# Power_Supply.net
KiCad netlist of a schematic drawn in Altium Designer
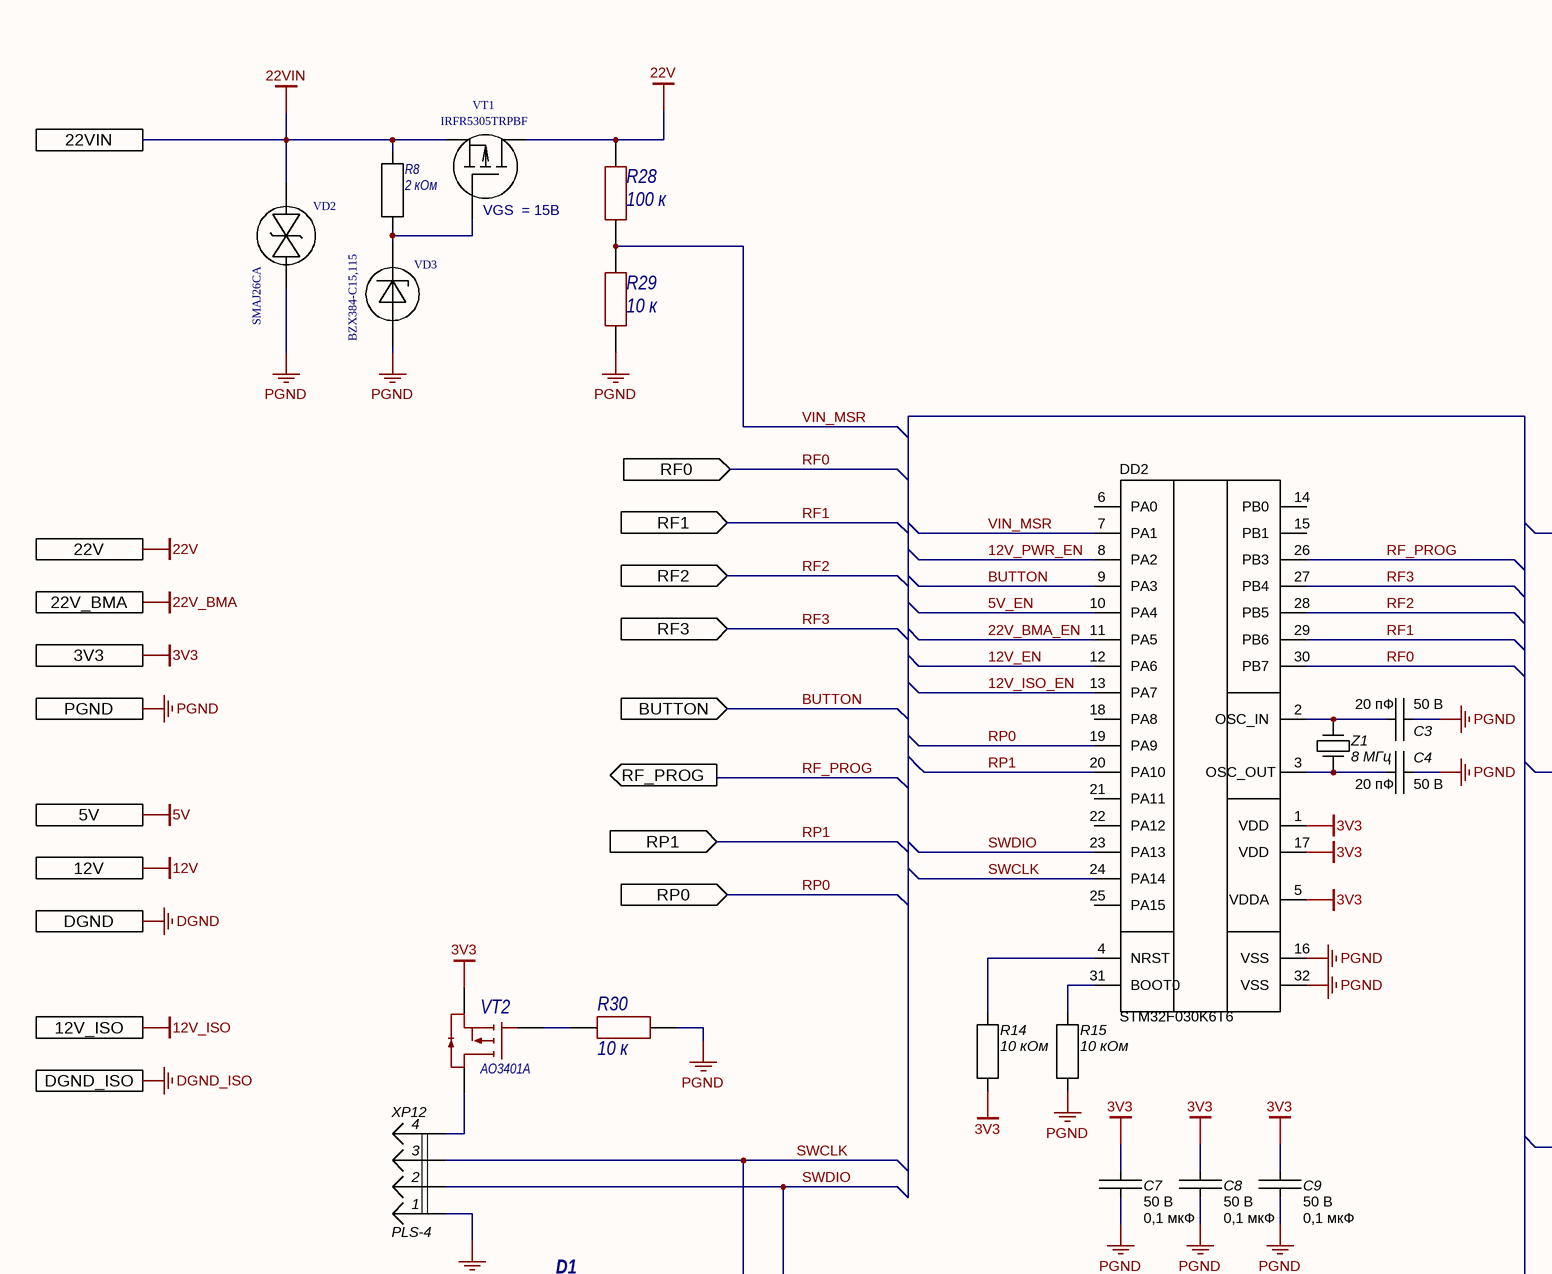
[diagram p0: Power Supply.SchDoc, top left]
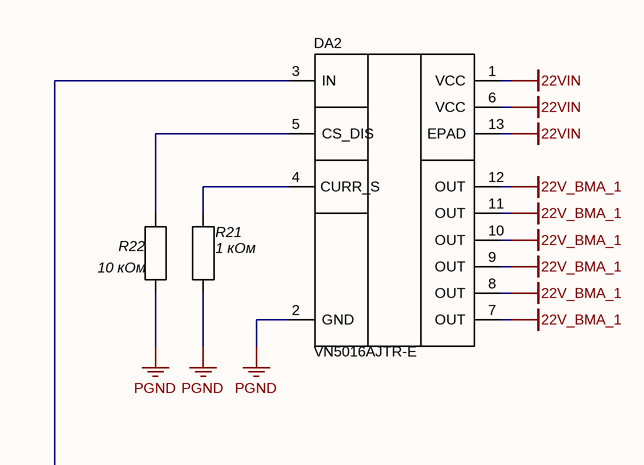
[diagram p1: Power Supply.SchDoc, top right]
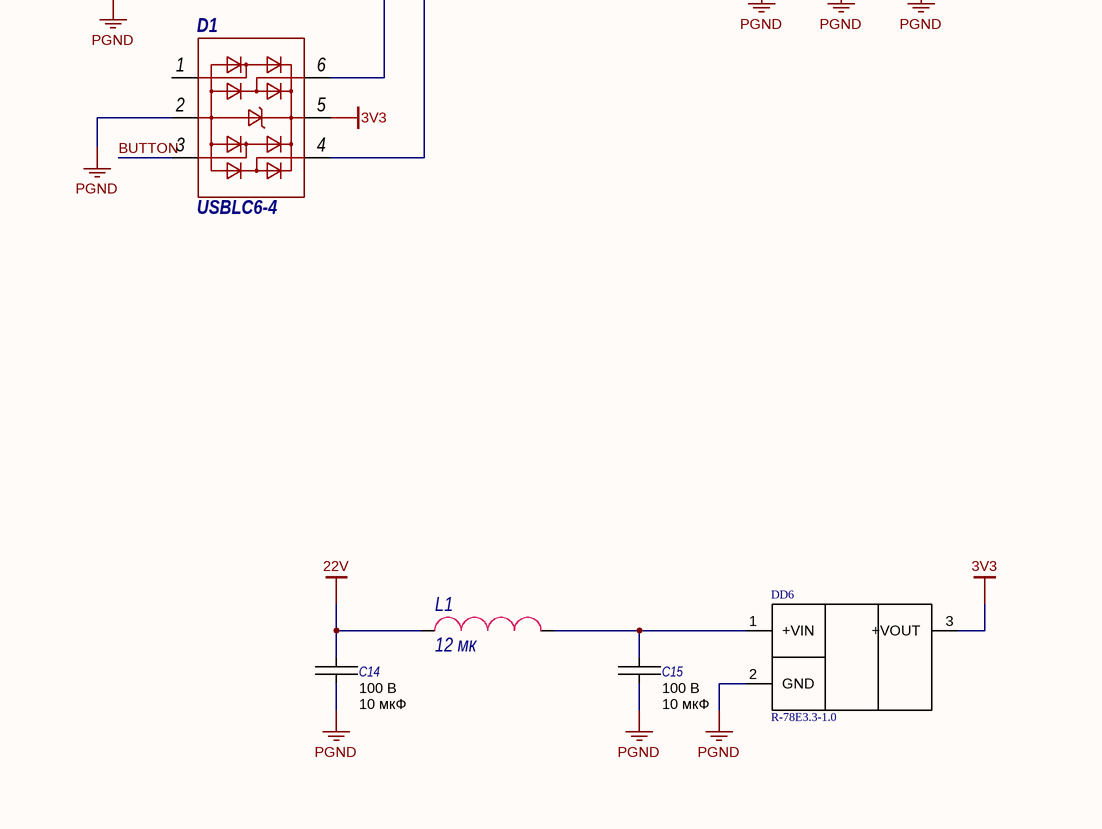
[diagram p2: Power Supply.SchDoc, bottom left]
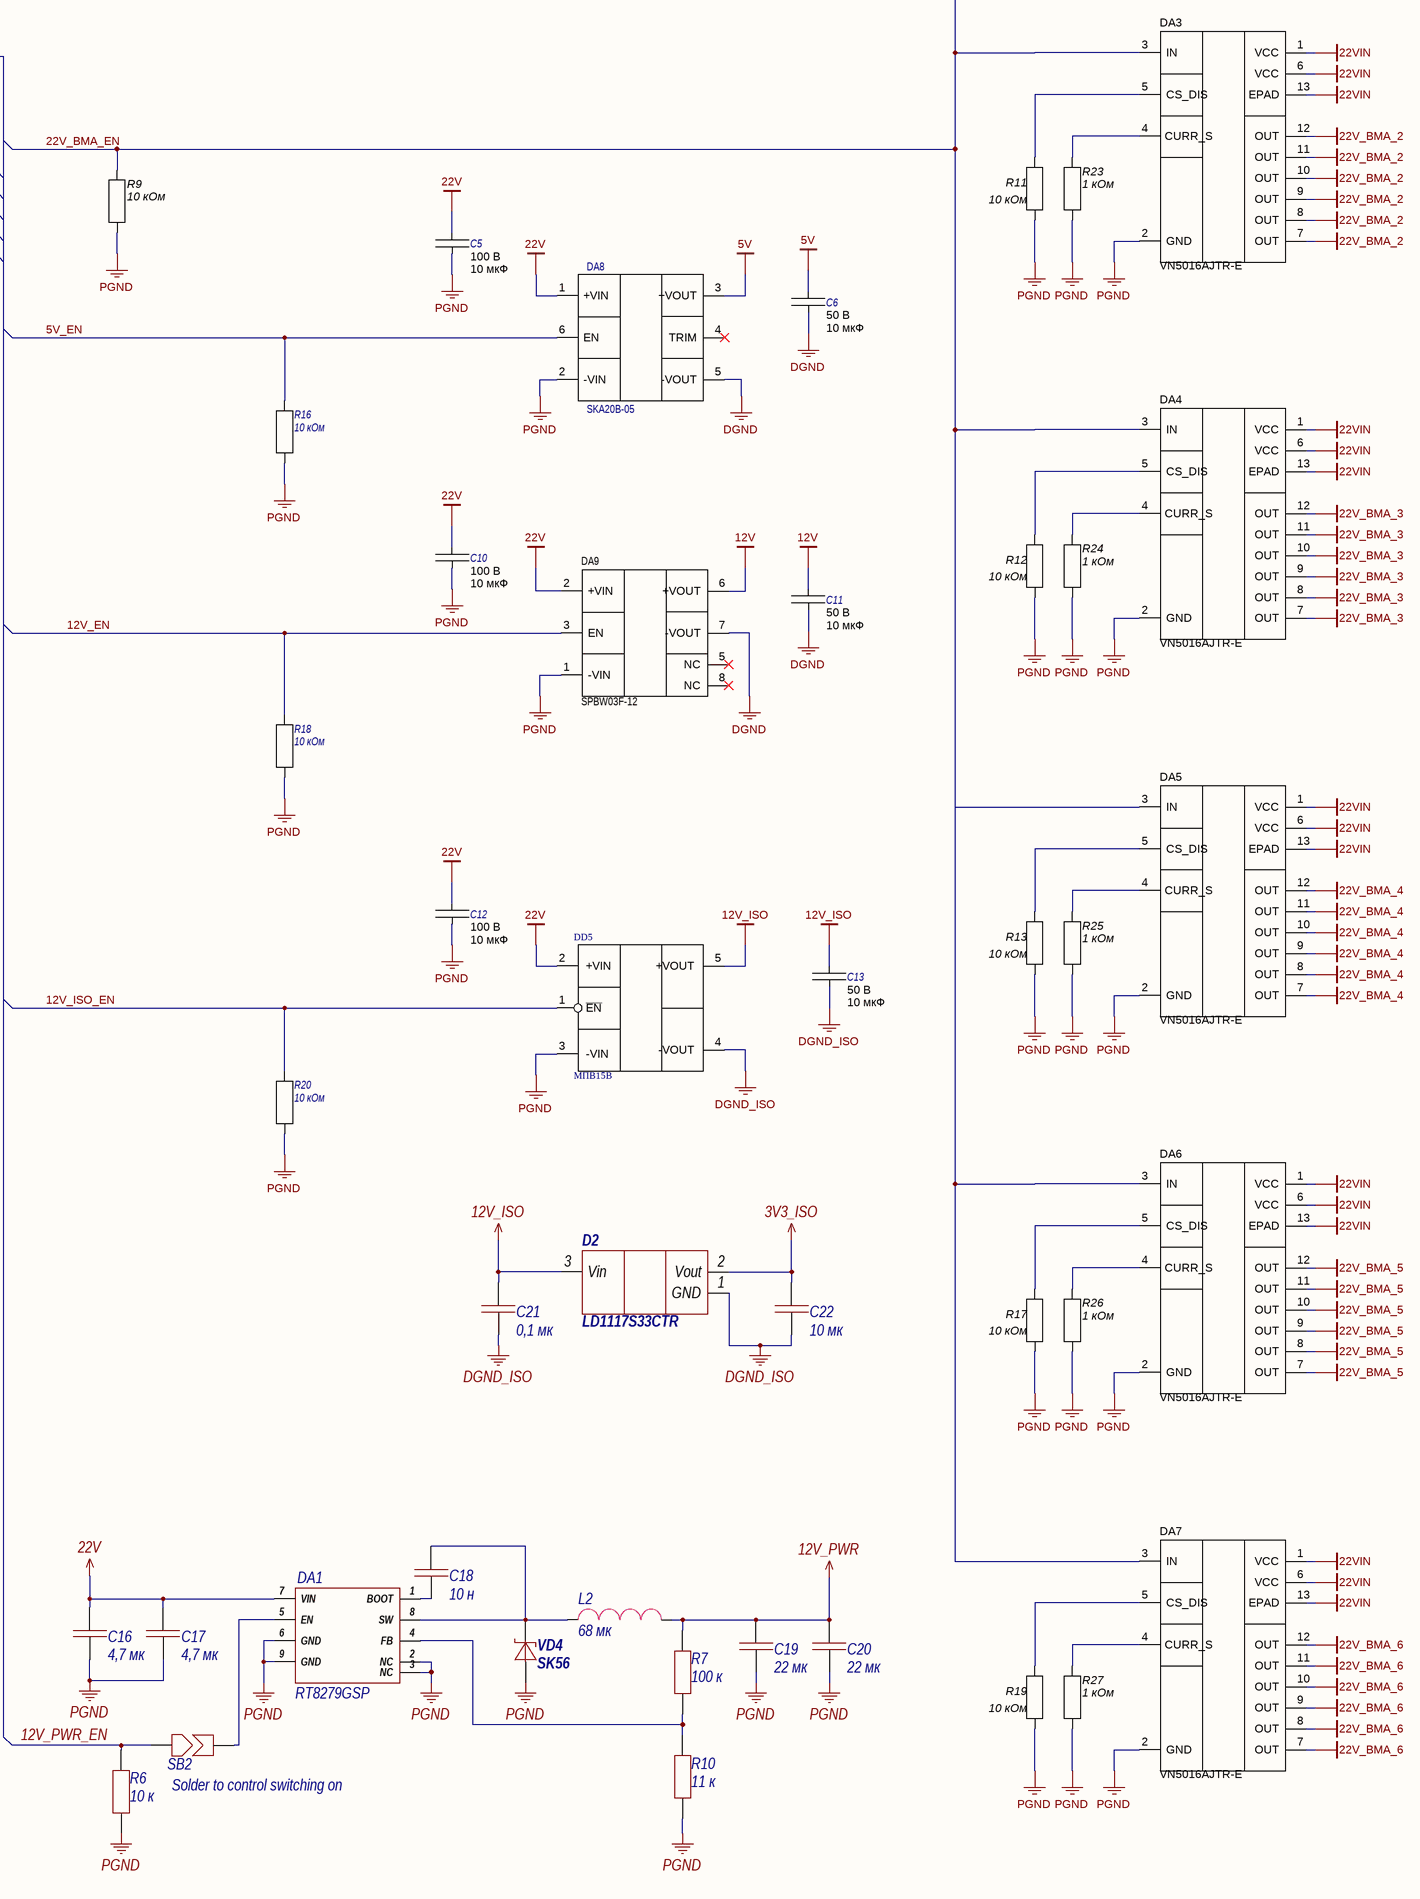
[diagram p3: Power Supply.SchDoc, bottom right]

(export (version "E")
  (design (tool "Eeschema 10.0.6"))
  (components
    (comp (ref "C3")
      (value "20 пФ")
      (footprint "C0603C")
      (description "SMD 0603 ; C0G(NP0); 20 пФ; 50 В")
      (fields
        (field (name "PART NUMBER") "CC0603JRNPO9BN200")
        (field (name "MANUFACTURER") "YAGEO")
        (field (name "VOLTAGE") "50 В")
      )
      (libsource (lib "Capacitors") (part "CC0603JRNPO9BN200"))
    )
    (comp (ref "C4")
      (value "20 пФ")
      (footprint "C0603C")
      (description "SMD 0603 ; C0G(NP0); 20 пФ; 50 В")
      (fields
        (field (name "PART NUMBER") "CC0603JRNPO9BN200")
        (field (name "MANUFACTURER") "YAGEO")
        (field (name "VOLTAGE") "50 В")
      )
      (libsource (lib "Capacitors") (part "CC0603JRNPO9BN200"))
    )
    (comp (ref "C5")
      (value "10 мкФ")
      (footprint "C2220C")
      (description "SMD 2220 ; X7R; 10 мкФ; 100 В")
      (fields
        (field (name "PART NUMBER") "22201C106MAT2A")
        (field (name "MANUFACTURER") "AVX")
        (field (name "VOLTAGE") "100 В")
      )
      (libsource (lib "Capacitors") (part "22201C106MAT2A"))
    )
    (comp (ref "C6")
      (value "10 мкФ")
      (footprint "C1210C")
      (description "SMD 1210; X7R; 10 мкФ; 50 В")
      (fields
        (field (name "PART NUMBER") "12105C106KAT2A")
        (field (name "MANUFACTURER") "AVX")
        (field (name "VOLTAGE") "50 В")
      )
      (libsource (lib "Capacitors") (part "12105C106KAT2A"))
    )
    (comp (ref "C7")
      (value "0,1 мкФ")
      (footprint "C0603C")
      (description "SMD 0603 ; X7R; 0,1 мкФ; 50 В")
      (fields
        (field (name "PART NUMBER") "CC0603KRX7R9BB104")
        (field (name "MANUFACTURER") "YAGEO")
        (field (name "VOLTAGE") "50 В")
      )
      (libsource (lib "Capacitors") (part "CC0603KRX7R9BB104"))
    )
    (comp (ref "C8")
      (value "0,1 мкФ")
      (footprint "C0603C")
      (description "SMD 0603 ; X7R; 0,1 мкФ; 50 В")
      (fields
        (field (name "PART NUMBER") "CC0603KRX7R9BB104")
        (field (name "MANUFACTURER") "YAGEO")
        (field (name "VOLTAGE") "50 В")
      )
      (libsource (lib "Capacitors") (part "CC0603KRX7R9BB104"))
    )
    (comp (ref "C9")
      (value "0,1 мкФ")
      (footprint "C0603C")
      (description "SMD 0603 ; X7R; 0,1 мкФ; 50 В")
      (fields
        (field (name "PART NUMBER") "CC0603KRX7R9BB104")
        (field (name "MANUFACTURER") "YAGEO")
        (field (name "VOLTAGE") "50 В")
      )
      (libsource (lib "Capacitors") (part "CC0603KRX7R9BB104"))
    )
    (comp (ref "C10")
      (value "10 мкФ")
      (footprint "C2220C")
      (description "SMD 2220 ; X7R; 10 мкФ; 100 В")
      (fields
        (field (name "PART NUMBER") "22201C106MAT2A")
        (field (name "MANUFACTURER") "AVX")
        (field (name "VOLTAGE") "100 В")
      )
      (libsource (lib "Capacitors") (part "22201C106MAT2A"))
    )
    (comp (ref "C11")
      (value "10 мкФ")
      (footprint "C1210C")
      (description "SMD 1210; X7R; 10 мкФ; 50 В")
      (fields
        (field (name "PART NUMBER") "12105C106KAT2A")
        (field (name "MANUFACTURER") "AVX")
        (field (name "VOLTAGE") "50 В")
      )
      (libsource (lib "Capacitors") (part "12105C106KAT2A"))
    )
    (comp (ref "C12")
      (value "10 мкФ")
      (footprint "C2220C")
      (description "SMD 2220 ; X7R; 10 мкФ; 100 В")
      (fields
        (field (name "PART NUMBER") "22201C106MAT2A")
        (field (name "MANUFACTURER") "AVX")
        (field (name "VOLTAGE") "100 В")
      )
      (libsource (lib "Capacitors") (part "22201C106MAT2A"))
    )
    (comp (ref "C13")
      (value "10 мкФ")
      (footprint "C1210C")
      (description "SMD 1210; X7R; 10 мкФ; 50 В")
      (fields
        (field (name "PART NUMBER") "12105C106KAT2A")
        (field (name "MANUFACTURER") "AVX")
        (field (name "VOLTAGE") "50 В")
      )
      (libsource (lib "Capacitors") (part "12105C106KAT2A"))
    )
    (comp (ref "C14")
      (value "10 мкФ")
      (footprint "C2220C")
      (description "SMD 2220 ; X7R; 10 мкФ; 100 В")
      (fields
        (field (name "PART NUMBER") "22201C106MAT2A")
        (field (name "MANUFACTURER") "AVX")
        (field (name "VOLTAGE") "100 В")
      )
      (libsource (lib "Capacitors") (part "22201C106MAT2A"))
    )
    (comp (ref "C15")
      (value "10 мкФ")
      (footprint "C2220C")
      (description "SMD 2220 ; X7R; 10 мкФ; 100 В")
      (fields
        (field (name "PART NUMBER") "22201C106MAT2A")
        (field (name "MANUFACTURER") "AVX")
        (field (name "VOLTAGE") "100 В")
      )
      (libsource (lib "Capacitors") (part "22201C106MAT2A"))
    )
    (comp (ref "C16")
      (value "4,7 мк")
      (footprint "1206C")
      (description "Конденсатор")
      (fields (field (name "PART NUMBER") "Capacitor_4,7u_10_50V_X7R_1206C") (field (name "TOLERANCE") "0,1"))
      (libsource (lib "Hydrolib") (part "Capacitor"))
    )
    (comp (ref "C17")
      (value "4,7 мк")
      (footprint "1206C")
      (description "Конденсатор")
      (fields (field (name "PART NUMBER") "Capacitor_4,7u_10_50V_X7R_1206C") (field (name "TOLERANCE") "0,1"))
      (libsource (lib "Hydrolib") (part "Capacitor"))
    )
    (comp (ref "C18")
      (value "10 н")
      (footprint "0603C")
      (description "Конденсатор")
      (fields (field (name "PART NUMBER") "Capacitor_10n_10_50V_X7R_0603C") (field (name "TOLERANCE") "0,1"))
      (libsource (lib "Hydrolib") (part "Capacitor"))
    )
    (comp (ref "C19")
      (value "22 мк")
      (footprint "1210C")
      (description "Конденсатор")
      (fields (field (name "PART NUMBER") "Capacitor_22u_10_25V_X7R_1210C") (field (name "TOLERANCE") "0,1"))
      (libsource (lib "Hydrolib") (part "Capacitor"))
    )
    (comp (ref "C20")
      (value "22 мк")
      (footprint "1210C")
      (description "Конденсатор")
      (fields (field (name "PART NUMBER") "Capacitor_22u_10_25V_X7R_1210C") (field (name "TOLERANCE") "0,1"))
      (libsource (lib "Hydrolib") (part "Capacitor"))
    )
    (comp (ref "C21")
      (value "0,1 мк")
      (footprint "0603C")
      (description "Конденсатор")
      (fields (field (name "PART NUMBER") "Capacitor_0,1u_10_50V_X7R_0603C") (field (name "TOLERANCE") "0,1"))
      (libsource (lib "Hydrolib") (part "Capacitor"))
    )
    (comp (ref "C22")
      (value "10 мк")
      (footprint "1210C")
      (description "Конденсатор")
      (fields (field (name "PART NUMBER") "Capacitor_10u_10_35V_X7R_1210C") (field (name "TOLERANCE") "0,1"))
      (libsource (lib "Hydrolib") (part "Capacitor"))
    )
    (comp (ref "D1")
      (value "USBLC6-4")
      (footprint "SOT23-6")
      (description "Сборка защитных диодов для USB")
      (libsource (lib "Hydrolib") (part "USBLC6-4"))
    )
    (comp (ref "D2")
      (value "LD1117S33CTR")
      (footprint "SOT223")
      (description "Линейный стабилизатор напряжения")
      (libsource (lib "Hydrolib") (part "LD1117S33CTR"))
    )
    (comp (ref "DA1")
      (value "RT8279GSP")
      (footprint "8SOP(Exposed_Pad)")
      (description "Преобразователь постоянного тока понижающий подстраиваемый выход 5А")
      (libsource (lib "Hydrolib") (part "RT8279GSP"))
    )
    (comp (ref "DA2")
      (value "VN5016AJTR-E")
      (footprint "PowerSSO-12")
      (description "High Current Power Switch")
      (fields (field (name "MANUFACTURER") "STMicroelectronics"))
      (libsource (lib "IC") (part "VN5016AJTR-E"))
    )
    (comp (ref "DA3")
      (value "VN5016AJTR-E")
      (footprint "PowerSSO-12")
      (description "High Current Power Switch")
      (fields (field (name "MANUFACTURER") "STMicroelectronics"))
      (libsource (lib "IC") (part "VN5016AJTR-E"))
    )
    (comp (ref "DA4")
      (value "VN5016AJTR-E")
      (footprint "PowerSSO-12")
      (description "High Current Power Switch")
      (fields (field (name "MANUFACTURER") "STMicroelectronics"))
      (libsource (lib "IC") (part "VN5016AJTR-E"))
    )
    (comp (ref "DA5")
      (value "VN5016AJTR-E")
      (footprint "PowerSSO-12")
      (description "High Current Power Switch")
      (fields (field (name "MANUFACTURER") "STMicroelectronics"))
      (libsource (lib "IC") (part "VN5016AJTR-E"))
    )
    (comp (ref "DA6")
      (value "VN5016AJTR-E")
      (footprint "PowerSSO-12")
      (description "High Current Power Switch")
      (fields (field (name "MANUFACTURER") "STMicroelectronics"))
      (libsource (lib "IC") (part "VN5016AJTR-E"))
    )
    (comp (ref "DA7")
      (value "VN5016AJTR-E")
      (footprint "PowerSSO-12")
      (description "High Current Power Switch")
      (fields (field (name "MANUFACTURER") "STMicroelectronics"))
      (libsource (lib "IC") (part "VN5016AJTR-E"))
    )
    (comp (ref "DA8")
      (value "SKA20B-05")
      (footprint "SKA20B05")
      (description "SKA20B-05, DC/DC преобразователь, 20Вт, вход 18-36В,выход 5В/4А")
      (libsource (lib "SKA20B-05") (part "Component_1"))
    )
    (comp (ref "DA9")
      (value "SPBW03F-12")
      (footprint "SIP8")
      (description "SPBW03F-12, DC/DC преобразователь, 3Вт, вход 9-36В,выход 12В/0.25А")
      (libsource (lib "SPBW03F-12") (part "SPBW03F-12"))
    )
    (comp (ref "DD2")
      (value "STM32F030K6T6")
      (footprint "LQFP32")
      (fields (field (name "MANUFACTURER") "STMicroelectronics"))
      (libsource (lib "IC") (part "STM32F030K6T6"))
    )
    (comp (ref "DD5")
      (value "МПВ15В")
      (footprint "МП_15_")
      (description "Switching regulator, Uвх = 27В, Uвых =12V")
      (fields (field (name "MANUFACTURER") "ИРБИС"))
      (libsource (lib "IC") (part "МПВ15В"))
    )
    (comp (ref "DD6")
      (value "R-78E3.3-1.0")
      (footprint "SIP3")
      (description "DC/DC, 24VIN 3V3 OUT")
      (fields (field (name "MANUFACTURER") "Recom"))
      (libsource (lib "IC") (part "R-78E3.3-1.0"))
    )
    (comp (ref "L1")
      (value "12 мк")
      (footprint "4.5x4_wired")
      (description "Индуктивность на 12 мкГн, номинальный ток 1,05 A")
      (fields (field (name "PART NUMBER") "SDR0403-120ML"))
      (libsource (lib "Hydrolib") (part "Inductance"))
    )
    (comp (ref "L2")
      (value "68 мк")
      (footprint "12.5x12.5")
      (description "Индуктивность на 68 мкГн, номинальный ток 2,65 A")
      (fields (field (name "PART NUMBER") "B82477R4683M100"))
      (libsource (lib "Hydrolib") (part "Inductance"))
    )
    (comp (ref "R6")
      (value "10 к")
      (footprint "0603R")
      (description "Резистор номиналом 10 кОм и точностью 1%")
      (fields (field (name "PART NUMBER") "Resistor_10k_1_0603") (field (name "TOLERANCE") "1%"))
      (libsource (lib "Hydrolib") (part "Resistor"))
    )
    (comp (ref "R7")
      (value "100 к")
      (footprint "0603R")
      (description "Резистор номиналом 100 кОм и точностью 1%")
      (fields (field (name "PART NUMBER") "Resistor_100k_1_0603") (field (name "TOLERANCE") "1%"))
      (libsource (lib "Hydrolib") (part "Resistor"))
    )
    (comp (ref "R8")
      (value "2 кОм")
      (footprint "C0603R")
      (description "SMD 0603; 0,1; 1%; 2 кОм")
      (fields (field (name "PART NUMBER") "RC0603FR-072KL") (field (name "POWER") "0,1"))
      (libsource (lib "Resistors") (part "RC0603FR-072KL"))
    )
    (comp (ref "R9")
      (value "10 кОм")
      (footprint "C0603R")
      (description "SMD 0603; 0,1; 1%; 10 кОм")
      (fields (field (name "PART NUMBER") "RC0603FR-0710KL") (field (name "POWER") "0,1"))
      (libsource (lib "Resistors") (part "RC0603FR-0710KL"))
    )
    (comp (ref "R10")
      (value "11 к")
      (footprint "0603R")
      (description "Резистор номиналом 11 кОм и точностью 1%")
      (fields (field (name "PART NUMBER") "Resistor_11k_1_0603") (field (name "TOLERANCE") "1%"))
      (libsource (lib "") (part "Resistor_2"))
    )
    (comp (ref "R11")
      (value "10 кОм")
      (footprint "C0603R")
      (description "SMD 0603; 0,1; 1%; 10 кОм")
      (fields (field (name "PART NUMBER") "RC0603FR-0710KL") (field (name "POWER") "0,1"))
      (libsource (lib "Resistors") (part "RC0603FR-0710KL"))
    )
    (comp (ref "R12")
      (value "10 кОм")
      (footprint "C0603R")
      (description "SMD 0603; 0,1; 1%; 10 кОм")
      (fields (field (name "PART NUMBER") "RC0603FR-0710KL") (field (name "POWER") "0,1"))
      (libsource (lib "Resistors") (part "RC0603FR-0710KL"))
    )
    (comp (ref "R13")
      (value "10 кОм")
      (footprint "C0603R")
      (description "SMD 0603; 0,1; 1%; 10 кОм")
      (fields (field (name "PART NUMBER") "RC0603FR-0710KL") (field (name "POWER") "0,1"))
      (libsource (lib "Resistors") (part "RC0603FR-0710KL"))
    )
    (comp (ref "R14")
      (value "10 кОм")
      (footprint "C0603R")
      (description "SMD 0603; 0,1; 1%; 10 кОм")
      (fields (field (name "PART NUMBER") "RC0603FR-0710KL") (field (name "POWER") "0,1"))
      (libsource (lib "Resistors") (part "RC0603FR-0710KL"))
    )
    (comp (ref "R15")
      (value "10 кОм")
      (footprint "C0603R")
      (description "SMD 0603; 0,1; 1%; 10 кОм")
      (fields (field (name "PART NUMBER") "RC0603FR-0710KL") (field (name "POWER") "0,1"))
      (libsource (lib "Resistors") (part "RC0603FR-0710KL"))
    )
    (comp (ref "R16")
      (value "10 кОм")
      (footprint "C0603R")
      (description "SMD 0603; 0,1; 1%; 10 кОм")
      (fields (field (name "PART NUMBER") "RC0603FR-0710KL") (field (name "POWER") "0,1"))
      (libsource (lib "Resistors") (part "RC0603FR-0710KL"))
    )
    (comp (ref "R17")
      (value "10 кОм")
      (footprint "C0603R")
      (description "SMD 0603; 0,1; 1%; 10 кОм")
      (fields (field (name "PART NUMBER") "RC0603FR-0710KL") (field (name "POWER") "0,1"))
      (libsource (lib "Resistors") (part "RC0603FR-0710KL"))
    )
    (comp (ref "R18")
      (value "10 кОм")
      (footprint "C0603R")
      (description "SMD 0603; 0,1; 1%; 10 кОм")
      (fields (field (name "PART NUMBER") "RC0603FR-0710KL") (field (name "POWER") "0,1"))
      (libsource (lib "Resistors") (part "RC0603FR-0710KL"))
    )
    (comp (ref "R19")
      (value "10 кОм")
      (footprint "C0603R")
      (description "SMD 0603; 0,1; 1%; 10 кОм")
      (fields (field (name "PART NUMBER") "RC0603FR-0710KL") (field (name "POWER") "0,1"))
      (libsource (lib "Resistors") (part "RC0603FR-0710KL"))
    )
    (comp (ref "R20")
      (value "10 кОм")
      (footprint "C0603R")
      (description "SMD 0603; 0,1; 1%; 10 кОм")
      (fields (field (name "PART NUMBER") "RC0603FR-0710KL") (field (name "POWER") "0,1"))
      (libsource (lib "Resistors") (part "RC0603FR-0710KL"))
    )
    (comp (ref "R21")
      (value "1 кОм")
      (footprint "C0603R")
      (description "SMD 0603; 0,1; 1%; 1 кОм")
      (fields (field (name "PART NUMBER") "RC0603FR-071KL") (field (name "POWER") "0,1"))
      (libsource (lib "Resistors") (part "RC0603FR-071KL"))
    )
    (comp (ref "R22")
      (value "10 кОм")
      (footprint "C0603R")
      (description "SMD 0603; 0,1; 1%; 10 кОм")
      (fields (field (name "PART NUMBER") "RC0603FR-0710KL") (field (name "POWER") "0,1"))
      (libsource (lib "Resistors") (part "RC0603FR-0710KL"))
    )
    (comp (ref "R23")
      (value "1 кОм")
      (footprint "C0603R")
      (description "SMD 0603; 0,1; 1%; 1 кОм")
      (fields (field (name "PART NUMBER") "RC0603FR-071KL") (field (name "POWER") "0,1"))
      (libsource (lib "Resistors") (part "RC0603FR-071KL"))
    )
    (comp (ref "R24")
      (value "1 кОм")
      (footprint "C0603R")
      (description "SMD 0603; 0,1; 1%; 1 кОм")
      (fields (field (name "PART NUMBER") "RC0603FR-071KL") (field (name "POWER") "0,1"))
      (libsource (lib "Resistors") (part "RC0603FR-071KL"))
    )
    (comp (ref "R25")
      (value "1 кОм")
      (footprint "C0603R")
      (description "SMD 0603; 0,1; 1%; 1 кОм")
      (fields (field (name "PART NUMBER") "RC0603FR-071KL") (field (name "POWER") "0,1"))
      (libsource (lib "Resistors") (part "RC0603FR-071KL"))
    )
    (comp (ref "R26")
      (value "1 кОм")
      (footprint "C0603R")
      (description "SMD 0603; 0,1; 1%; 1 кОм")
      (fields (field (name "PART NUMBER") "RC0603FR-071KL") (field (name "POWER") "0,1"))
      (libsource (lib "Resistors") (part "RC0603FR-071KL"))
    )
    (comp (ref "R27")
      (value "1 кОм")
      (footprint "C0603R")
      (description "SMD 0603; 0,1; 1%; 1 кОм")
      (fields (field (name "PART NUMBER") "RC0603FR-071KL") (field (name "POWER") "0,1"))
      (libsource (lib "Resistors") (part "RC0603FR-071KL"))
    )
    (comp (ref "R28")
      (value "100 к")
      (footprint "0603R")
      (description "Резистор номиналом 100 кОм и точностью 1%")
      (fields (field (name "PART NUMBER") "Resistor_100k_1_0603") (field (name "TOLERANCE") "1%"))
      (libsource (lib "Hydrolib") (part "Resistor"))
    )
    (comp (ref "R29")
      (value "10 к")
      (footprint "0603R")
      (description "Резистор номиналом 10 кОм и точностью 1%")
      (fields (field (name "PART NUMBER") "Resistor_10k_1_0603") (field (name "TOLERANCE") "1%"))
      (libsource (lib "Hydrolib") (part "Resistor"))
    )
    (comp (ref "R30")
      (value "10 к")
      (footprint "0603R")
      (description "Резистор номиналом 10 кОм и точностью 1%")
      (fields (field (name "PART NUMBER") "Resistor_10k_1_0603") (field (name "TOLERANCE") "1%"))
      (libsource (lib "") (part "Resistor_1"))
    )
    (comp (ref "SB2")
      (value "SB")
      (footprint "0805SB")
      (description "Solder bridge, мост припоя, запаиваемая перемычка, net tie, jumper")
      (libsource (lib "Hydrolib") (part "SB"))
    )
    (comp (ref "VD2")
      (value "SMAJ26CA")
      (footprint "DO-214AC")
      (description "TVS 26 В")
      (fields (field (name "VOLTAGE") "26V") (field (name "POWER") "400W"))
      (libsource (lib "VD") (part "SMAJ26CA"))
    )
    (comp (ref "VD3")
      (value "BZX384-C15,115")
      (footprint "SOD-123")
      (description "Zener, 15В")
      (fields (field (name "MANUFACTURER") "Nexperia"))
      (libsource (lib "VD") (part "BZX384-C15,115"))
    )
    (comp (ref "VD4")
      (value "SK56")
      (footprint "SMC")
      (description "Диод шоттки на 60 В, ном. ток 5 А")
      (libsource (lib "Hydrolib") (part "Schottky_diode"))
    )
    (comp (ref "VT1")
      (value "IRFR5305TRPBF")
      (footprint "D-PAK")
      (description "P MOSFET")
      (fields (field (name "MANUFACTURER") "Infineon"))
      (libsource (lib "VT") (part "IRFR5305TRPBF"))
    )
    (comp (ref "VT2")
      (value "AO3401A")
      (footprint "SOT23-3")
      (description "P-канальный MOSFET")
      (libsource (lib "Hydrolib") (part "MOSFET P-channel 2"))
    )
    (comp (ref "XP12") (value "PLS-4") (footprint "PLS-4") (libsource (lib "Conectors") (part "PLS-4")))
    (comp (ref "Z1")
      (value "8 МГц")
      (footprint "HC-49SM")
      (description "8.000MHzHC-49SM")
      (libsource (lib "IC") (part "8.000MHzHC-49SM"))
    )
  )
  (nets
    (net (code "1") (name "/5V_EN") (class "Default")
      (node (ref "DA8") (pin "6") (pinfunction "EN_6") (pintype "passive"))
      (node (ref "DD2") (pin "10") (pinfunction "PA4_10") (pintype "passive"))
      (node (ref "R16") (pin "2") (pinfunction "2_2") (pintype "passive"))
    )
    (net (code "2") (name "/12V_EN") (class "Default")
      (node (ref "DA9") (pin "3") (pinfunction "EN_3") (pintype "passive"))
      (node (ref "DD2") (pin "12") (pinfunction "PA6_12") (pintype "passive"))
      (node (ref "R18") (pin "2") (pinfunction "2_2") (pintype "passive"))
    )
    (net (code "3") (name "/12V_ISO_EN") (class "Default")
      (node (ref "DD2") (pin "13") (pinfunction "PA7_13") (pintype "passive"))
      (node (ref "DD5") (pin "1") (pinfunction "~{EN}_1") (pintype "passive"))
      (node (ref "R20") (pin "2") (pinfunction "2_2") (pintype "passive"))
    )
    (net (code "4") (name "/12V_PWR_EN") (class "Default")
      (node (ref "DD2") (pin "8") (pinfunction "PA2_8") (pintype "passive"))
      (node (ref "R6") (pin "2") (pinfunction "2_2") (pintype "passive"))
      (node (ref "SB2") (pin "2") (pinfunction "2_2") (pintype "passive"))
    )
    (net (code "5") (name "/22V_BMA_EN") (class "Default")
      (node (ref "DA2") (pin "3") (pinfunction "IN_3") (pintype "passive"))
      (node (ref "DA3") (pin "3") (pinfunction "IN_3") (pintype "passive"))
      (node (ref "DA4") (pin "3") (pinfunction "IN_3") (pintype "passive"))
      (node (ref "DA5") (pin "3") (pinfunction "IN_3") (pintype "passive"))
      (node (ref "DA6") (pin "3") (pinfunction "IN_3") (pintype "passive"))
      (node (ref "DA7") (pin "3") (pinfunction "IN_3") (pintype "passive"))
      (node (ref "DD2") (pin "11") (pinfunction "PA5_11") (pintype "passive"))
      (node (ref "R9") (pin "1") (pinfunction "1_1") (pintype "passive"))
    )
    (net (code "6") (name "/BUTTON") (class "Default")
      (node (ref "D1") (pin "3") (pinfunction "11_3") (pintype "passive"))
      (node (ref "DD2") (pin "9") (pinfunction "PA3_9") (pintype "passive"))
    )
    (net (code "7") (name "/RF0") (class "Default")
      (node (ref "DD2") (pin "30") (pinfunction "PB7_30") (pintype "passive"))
    )
    (net (code "8") (name "/RF1") (class "Default")
      (node (ref "DD2") (pin "29") (pinfunction "PB6_29") (pintype "passive"))
    )
    (net (code "9") (name "/RF2") (class "Default")
      (node (ref "DD2") (pin "28") (pinfunction "PB5_28") (pintype "passive"))
    )
    (net (code "10") (name "/RF3") (class "Default")
      (node (ref "DD2") (pin "27") (pinfunction "PB4_27") (pintype "passive"))
    )
    (net (code "11") (name "/RF_PROG") (class "Default")
      (node (ref "DD2") (pin "26") (pinfunction "PB3_26") (pintype "passive"))
    )
    (net (code "12") (name "/RP0") (class "Default")
      (node (ref "DD2") (pin "19") (pinfunction "PA9_19") (pintype "passive"))
    )
    (net (code "13") (name "/RP1") (class "Default")
      (node (ref "DD2") (pin "20") (pinfunction "PA10_20") (pintype "passive"))
    )
    (net (code "14") (name "/SWCLK") (class "Default")
      (node (ref "D1") (pin "6") (pinfunction "14_6") (pintype "passive"))
      (node (ref "DD2") (pin "24") (pinfunction "PA14_24") (pintype "passive"))
      (node (ref "XP12") (pin "3") (pinfunction "3_3") (pintype "passive"))
    )
    (net (code "15") (name "/SWDIO") (class "Default")
      (node (ref "D1") (pin "4") (pinfunction "12_4") (pintype "passive"))
      (node (ref "DD2") (pin "23") (pinfunction "PA13_23") (pintype "passive"))
      (node (ref "XP12") (pin "2") (pinfunction "2_2") (pintype "passive"))
    )
    (net (code "16") (name "/VIN_MSR") (class "Default")
      (node (ref "DD2") (pin "7") (pinfunction "PA1_7") (pintype "passive"))
      (node (ref "R28") (pin "1") (pinfunction "1_1") (pintype "passive"))
      (node (ref "R29") (pin "2") (pinfunction "2_2") (pintype "passive"))
    )
    (net (code "17") (name "3V3") (class "Default")
      (node (ref "C7") (pin "1") (pinfunction "1_1") (pintype "passive"))
      (node (ref "C8") (pin "1") (pinfunction "1_1") (pintype "passive"))
      (node (ref "C9") (pin "1") (pinfunction "1_1") (pintype "passive"))
      (node (ref "D1") (pin "5") (pinfunction "13_5") (pintype "passive"))
      (node (ref "DD2") (pin "1") (pinfunction "VDD_1") (pintype "passive"))
      (node (ref "DD2") (pin "17") (pinfunction "VDD_17") (pintype "passive"))
      (node (ref "DD2") (pin "5") (pinfunction "VDDA_5") (pintype "passive"))
      (node (ref "DD6") (pin "3") (pinfunction "+VOUT_3") (pintype "power_in"))
      (node (ref "R14") (pin "1") (pinfunction "1_1") (pintype "passive"))
      (node (ref "VT2") (pin "2") (pinfunction "2_2") (pintype "passive"))
    )
    (net (code "18") (name "3V3_ISO") (class "Default")
      (node (ref "C22") (pin "2") (pinfunction "2_2") (pintype "passive"))
      (node (ref "D2") (pin "2") (pinfunction "Vout_2") (pintype "passive"))
    )
    (net (code "19") (name "5V") (class "Default")
      (node (ref "C6") (pin "1") (pinfunction "1_1") (pintype "passive"))
      (node (ref "DA8") (pin "3") (pinfunction "+VOUT_3") (pintype "passive"))
    )
    (net (code "20") (name "12V") (class "Default")
      (node (ref "C11") (pin "1") (pinfunction "1_1") (pintype "passive"))
      (node (ref "DA9") (pin "6") (pinfunction "+VOUT_6") (pintype "passive"))
    )
    (net (code "21") (name "12V_ISO") (class "Default")
      (node (ref "C13") (pin "1") (pinfunction "1_1") (pintype "passive"))
      (node (ref "C21") (pin "2") (pinfunction "2_2") (pintype "passive"))
      (node (ref "D2") (pin "3") (pinfunction "Vin_3") (pintype "passive"))
      (node (ref "DD5") (pin "5") (pinfunction "+VOUT_5") (pintype "passive"))
    )
    (net (code "22") (name "12V_PWR") (class "Default")
      (node (ref "C19") (pin "2") (pinfunction "2_2") (pintype "passive"))
      (node (ref "C20") (pin "2") (pinfunction "2_2") (pintype "passive"))
      (node (ref "L2") (pin "2") (pinfunction "2_2") (pintype "passive"))
      (node (ref "R7") (pin "2") (pinfunction "2_2") (pintype "passive"))
    )
    (net (code "23") (name "22V") (class "Default")
      (node (ref "C10") (pin "1") (pinfunction "1_1") (pintype "passive"))
      (node (ref "C12") (pin "1") (pinfunction "1_1") (pintype "passive"))
      (node (ref "C14") (pin "1") (pinfunction "1_1") (pintype "passive"))
      (node (ref "C16") (pin "2") (pinfunction "2_2") (pintype "passive"))
      (node (ref "C17") (pin "2") (pinfunction "2_2") (pintype "passive"))
      (node (ref "C5") (pin "1") (pinfunction "1_1") (pintype "passive"))
      (node (ref "DA1") (pin "7") (pinfunction "VIN_7") (pintype "passive"))
      (node (ref "DA8") (pin "1") (pinfunction "+VIN_1") (pintype "passive"))
      (node (ref "DA9") (pin "2") (pinfunction "+VIN_2") (pintype "passive"))
      (node (ref "DD5") (pin "2") (pinfunction "+VIN_2") (pintype "passive"))
      (node (ref "L1") (pin "1") (pinfunction "1_1") (pintype "passive"))
      (node (ref "R28") (pin "2") (pinfunction "2_2") (pintype "passive"))
      (node (ref "VT1") (pin "2") (pinfunction "D_2") (pintype "passive"))
    )
    (net (code "24") (name "22VIN") (class "Default")
      (node (ref "DA2") (pin "1") (pinfunction "VCC_1") (pintype "passive"))
      (node (ref "DA2") (pin "13") (pinfunction "EPAD_13") (pintype "passive"))
      (node (ref "DA2") (pin "6") (pinfunction "VCC_6") (pintype "passive"))
      (node (ref "DA3") (pin "1") (pinfunction "VCC_1") (pintype "passive"))
      (node (ref "DA3") (pin "13") (pinfunction "EPAD_13") (pintype "passive"))
      (node (ref "DA3") (pin "6") (pinfunction "VCC_6") (pintype "passive"))
      (node (ref "DA4") (pin "1") (pinfunction "VCC_1") (pintype "passive"))
      (node (ref "DA4") (pin "13") (pinfunction "EPAD_13") (pintype "passive"))
      (node (ref "DA4") (pin "6") (pinfunction "VCC_6") (pintype "passive"))
      (node (ref "DA5") (pin "1") (pinfunction "VCC_1") (pintype "passive"))
      (node (ref "DA5") (pin "13") (pinfunction "EPAD_13") (pintype "passive"))
      (node (ref "DA5") (pin "6") (pinfunction "VCC_6") (pintype "passive"))
      (node (ref "DA6") (pin "1") (pinfunction "VCC_1") (pintype "passive"))
      (node (ref "DA6") (pin "13") (pinfunction "EPAD_13") (pintype "passive"))
      (node (ref "DA6") (pin "6") (pinfunction "VCC_6") (pintype "passive"))
      (node (ref "DA7") (pin "1") (pinfunction "VCC_1") (pintype "passive"))
      (node (ref "DA7") (pin "13") (pinfunction "EPAD_13") (pintype "passive"))
      (node (ref "DA7") (pin "6") (pinfunction "VCC_6") (pintype "passive"))
      (node (ref "R8") (pin "1") (pinfunction "1_1") (pintype "passive"))
      (node (ref "VD2") (pin "1") (pinfunction "C_1") (pintype "passive"))
      (node (ref "VT1") (pin "3") (pinfunction "S_3") (pintype "passive"))
    )
    (net (code "26") (name "22V_BMA_1") (class "Default")
      (node (ref "DA2") (pin "10") (pinfunction "OUT_10") (pintype "passive"))
      (node (ref "DA2") (pin "11") (pinfunction "OUT_11") (pintype "passive"))
      (node (ref "DA2") (pin "12") (pinfunction "OUT_12") (pintype "passive"))
      (node (ref "DA2") (pin "7") (pinfunction "OUT_7") (pintype "passive"))
      (node (ref "DA2") (pin "8") (pinfunction "OUT_8") (pintype "passive"))
      (node (ref "DA2") (pin "9") (pinfunction "OUT_9") (pintype "passive"))
    )
    (net (code "27") (name "22V_BMA_2") (class "Default")
      (node (ref "DA3") (pin "10") (pinfunction "OUT_10") (pintype "passive"))
      (node (ref "DA3") (pin "11") (pinfunction "OUT_11") (pintype "passive"))
      (node (ref "DA3") (pin "12") (pinfunction "OUT_12") (pintype "passive"))
      (node (ref "DA3") (pin "7") (pinfunction "OUT_7") (pintype "passive"))
      (node (ref "DA3") (pin "8") (pinfunction "OUT_8") (pintype "passive"))
      (node (ref "DA3") (pin "9") (pinfunction "OUT_9") (pintype "passive"))
    )
    (net (code "28") (name "22V_BMA_3") (class "Default")
      (node (ref "DA4") (pin "10") (pinfunction "OUT_10") (pintype "passive"))
      (node (ref "DA4") (pin "11") (pinfunction "OUT_11") (pintype "passive"))
      (node (ref "DA4") (pin "12") (pinfunction "OUT_12") (pintype "passive"))
      (node (ref "DA4") (pin "7") (pinfunction "OUT_7") (pintype "passive"))
      (node (ref "DA4") (pin "8") (pinfunction "OUT_8") (pintype "passive"))
      (node (ref "DA4") (pin "9") (pinfunction "OUT_9") (pintype "passive"))
    )
    (net (code "29") (name "22V_BMA_4") (class "Default")
      (node (ref "DA5") (pin "10") (pinfunction "OUT_10") (pintype "passive"))
      (node (ref "DA5") (pin "11") (pinfunction "OUT_11") (pintype "passive"))
      (node (ref "DA5") (pin "12") (pinfunction "OUT_12") (pintype "passive"))
      (node (ref "DA5") (pin "7") (pinfunction "OUT_7") (pintype "passive"))
      (node (ref "DA5") (pin "8") (pinfunction "OUT_8") (pintype "passive"))
      (node (ref "DA5") (pin "9") (pinfunction "OUT_9") (pintype "passive"))
    )
    (net (code "30") (name "22V_BMA_5") (class "Default")
      (node (ref "DA6") (pin "10") (pinfunction "OUT_10") (pintype "passive"))
      (node (ref "DA6") (pin "11") (pinfunction "OUT_11") (pintype "passive"))
      (node (ref "DA6") (pin "12") (pinfunction "OUT_12") (pintype "passive"))
      (node (ref "DA6") (pin "7") (pinfunction "OUT_7") (pintype "passive"))
      (node (ref "DA6") (pin "8") (pinfunction "OUT_8") (pintype "passive"))
      (node (ref "DA6") (pin "9") (pinfunction "OUT_9") (pintype "passive"))
    )
    (net (code "31") (name "22V_BMA_6") (class "Default")
      (node (ref "DA7") (pin "10") (pinfunction "OUT_10") (pintype "passive"))
      (node (ref "DA7") (pin "11") (pinfunction "OUT_11") (pintype "passive"))
      (node (ref "DA7") (pin "12") (pinfunction "OUT_12") (pintype "passive"))
      (node (ref "DA7") (pin "7") (pinfunction "OUT_7") (pintype "passive"))
      (node (ref "DA7") (pin "8") (pinfunction "OUT_8") (pintype "passive"))
      (node (ref "DA7") (pin "9") (pinfunction "OUT_9") (pintype "passive"))
    )
    (net (code "32") (name "DGND") (class "Default")
      (node (ref "C11") (pin "2") (pinfunction "2_2") (pintype "passive"))
      (node (ref "C6") (pin "2") (pinfunction "2_2") (pintype "passive"))
      (node (ref "DA8") (pin "5") (pinfunction "-VOUT_5") (pintype "passive"))
      (node (ref "DA9") (pin "7") (pinfunction "-VOUT_7") (pintype "passive"))
    )
    (net (code "33") (name "DGND_ISO") (class "Default")
      (node (ref "C13") (pin "2") (pinfunction "2_2") (pintype "passive"))
      (node (ref "C21") (pin "1") (pinfunction "1_1") (pintype "passive"))
      (node (ref "C22") (pin "1") (pinfunction "1_1") (pintype "passive"))
      (node (ref "D2") (pin "1") (pinfunction "GND_1") (pintype "passive"))
      (node (ref "DD5") (pin "4") (pinfunction "-VOUT_4") (pintype "passive"))
    )
    (net (code "34") (name "Net-(DA1-BOOT)") (class "Default")
      (node (ref "C18") (pin "1") (pinfunction "1_1") (pintype "passive"))
      (node (ref "DA1") (pin "1") (pinfunction "BOOT_1") (pintype "passive"))
    )
    (net (code "35") (name "Net-(DA1-EN)") (class "Default")
      (node (ref "DA1") (pin "5") (pinfunction "EN_5") (pintype "passive"))
      (node (ref "SB2") (pin "1") (pinfunction "1_1") (pintype "passive"))
    )
    (net (code "36") (name "Net-(DA1-FB)") (class "Default")
      (node (ref "DA1") (pin "4") (pinfunction "FB_4") (pintype "passive"))
      (node (ref "R10") (pin "1") (pinfunction "1_1") (pintype "passive"))
      (node (ref "R7") (pin "1") (pinfunction "1_1") (pintype "passive"))
    )
    (net (code "37") (name "Net-(DA1-SW)") (class "Default")
      (node (ref "C18") (pin "2") (pinfunction "2_2") (pintype "passive"))
      (node (ref "DA1") (pin "8") (pinfunction "SW_8") (pintype "passive"))
      (node (ref "L2") (pin "1") (pinfunction "1_1") (pintype "passive"))
      (node (ref "VD4") (pin "2") (pinfunction "2_2") (pintype "passive"))
    )
    (net (code "38") (name "Net-(DA2-CS_DIS)") (class "Default")
      (node (ref "DA2") (pin "5") (pinfunction "CS_DIS_5") (pintype "passive"))
      (node (ref "R22") (pin "1") (pinfunction "1_1") (pintype "passive"))
    )
    (net (code "39") (name "Net-(DA2-CURR_S)") (class "Default")
      (node (ref "DA2") (pin "4") (pinfunction "CURR_S_4") (pintype "passive"))
      (node (ref "R21") (pin "1") (pinfunction "1_1") (pintype "passive"))
    )
    (net (code "40") (name "Net-(DA3-CS_DIS)") (class "Default")
      (node (ref "DA3") (pin "5") (pinfunction "CS_DIS_5") (pintype "passive"))
      (node (ref "R11") (pin "1") (pinfunction "1_1") (pintype "passive"))
    )
    (net (code "41") (name "Net-(DA3-CURR_S)") (class "Default")
      (node (ref "DA3") (pin "4") (pinfunction "CURR_S_4") (pintype "passive"))
      (node (ref "R23") (pin "1") (pinfunction "1_1") (pintype "passive"))
    )
    (net (code "42") (name "Net-(DA4-CS_DIS)") (class "Default")
      (node (ref "DA4") (pin "5") (pinfunction "CS_DIS_5") (pintype "passive"))
      (node (ref "R12") (pin "1") (pinfunction "1_1") (pintype "passive"))
    )
    (net (code "43") (name "Net-(DA4-CURR_S)") (class "Default")
      (node (ref "DA4") (pin "4") (pinfunction "CURR_S_4") (pintype "passive"))
      (node (ref "R24") (pin "1") (pinfunction "1_1") (pintype "passive"))
    )
    (net (code "44") (name "Net-(DA5-CS_DIS)") (class "Default")
      (node (ref "DA5") (pin "5") (pinfunction "CS_DIS_5") (pintype "passive"))
      (node (ref "R13") (pin "1") (pinfunction "1_1") (pintype "passive"))
    )
    (net (code "45") (name "Net-(DA5-CURR_S)") (class "Default")
      (node (ref "DA5") (pin "4") (pinfunction "CURR_S_4") (pintype "passive"))
      (node (ref "R25") (pin "1") (pinfunction "1_1") (pintype "passive"))
    )
    (net (code "46") (name "Net-(DA6-CS_DIS)") (class "Default")
      (node (ref "DA6") (pin "5") (pinfunction "CS_DIS_5") (pintype "passive"))
      (node (ref "R17") (pin "1") (pinfunction "1_1") (pintype "passive"))
    )
    (net (code "47") (name "Net-(DA6-CURR_S)") (class "Default")
      (node (ref "DA6") (pin "4") (pinfunction "CURR_S_4") (pintype "passive"))
      (node (ref "R26") (pin "1") (pinfunction "1_1") (pintype "passive"))
    )
    (net (code "48") (name "Net-(DA7-CS_DIS)") (class "Default")
      (node (ref "DA7") (pin "5") (pinfunction "CS_DIS_5") (pintype "passive"))
      (node (ref "R19") (pin "1") (pinfunction "1_1") (pintype "passive"))
    )
    (net (code "49") (name "Net-(DA7-CURR_S)") (class "Default")
      (node (ref "DA7") (pin "4") (pinfunction "CURR_S_4") (pintype "passive"))
      (node (ref "R27") (pin "1") (pinfunction "1_1") (pintype "passive"))
    )
    (net (code "50") (name "Net-(DD2-BOOT0)") (class "Default")
      (node (ref "DD2") (pin "31") (pinfunction "BOOT0_31") (pintype "passive"))
      (node (ref "R15") (pin "2") (pinfunction "2_2") (pintype "passive"))
    )
    (net (code "51") (name "Net-(DD2-NRST)") (class "Default")
      (node (ref "DD2") (pin "4") (pinfunction "NRST_4") (pintype "passive"))
      (node (ref "R14") (pin "2") (pinfunction "2_2") (pintype "passive"))
    )
    (net (code "52") (name "Net-(DD2-OSC_IN)") (class "Default")
      (node (ref "C3") (pin "2") (pinfunction "2_2") (pintype "passive"))
      (node (ref "DD2") (pin "2") (pinfunction "OSC_IN_2") (pintype "passive"))
      (node (ref "Z1") (pin "2") (pinfunction "OSC2_2") (pintype "passive"))
    )
    (net (code "53") (name "Net-(DD2-OSC_OUT)") (class "Default")
      (node (ref "C4") (pin "2") (pinfunction "2_2") (pintype "passive"))
      (node (ref "DD2") (pin "3") (pinfunction "OSC_OUT_3") (pintype "passive"))
      (node (ref "Z1") (pin "1") (pinfunction "OSC1_1") (pintype "passive"))
    )
    (net (code "54") (name "Net-(DD6-+VIN)") (class "Default")
      (node (ref "C15") (pin "1") (pinfunction "1_1") (pintype "passive"))
      (node (ref "DD6") (pin "1") (pinfunction "+VIN_1") (pintype "power_in"))
      (node (ref "L1") (pin "2") (pinfunction "2_2") (pintype "passive"))
    )
    (net (code "55") (name "Net-(R30-Pad2)") (class "Default")
      (node (ref "R30") (pin "2") (pinfunction "2_2") (pintype "passive"))
      (node (ref "VT2") (pin "1") (pinfunction "1_1") (pintype "passive"))
    )
    (net (code "56") (name "Net-(VD3-CATHODE)") (class "Default")
      (node (ref "R8") (pin "2") (pinfunction "2_2") (pintype "passive"))
      (node (ref "VD3") (pin "1") (pinfunction "CATHODE_1") (pintype "passive"))
      (node (ref "VT1") (pin "1") (pinfunction "G_1") (pintype "passive"))
    )
    (net (code "57") (name "Net-(VT2-Pad3)") (class "Default")
      (node (ref "VT2") (pin "3") (pinfunction "3_3") (pintype "passive"))
      (node (ref "XP12") (pin "4") (pinfunction "4_4") (pintype "passive"))
    )
    (net (code "58") (name "PGND") (class "Default")
      (node (ref "C10") (pin "2") (pinfunction "2_2") (pintype "passive"))
      (node (ref "C12") (pin "2") (pinfunction "2_2") (pintype "passive"))
      (node (ref "C14") (pin "2") (pinfunction "2_2") (pintype "passive"))
      (node (ref "C15") (pin "2") (pinfunction "2_2") (pintype "passive"))
      (node (ref "C16") (pin "1") (pinfunction "1_1") (pintype "passive"))
      (node (ref "C17") (pin "1") (pinfunction "1_1") (pintype "passive"))
      (node (ref "C19") (pin "1") (pinfunction "1_1") (pintype "passive"))
      (node (ref "C20") (pin "1") (pinfunction "1_1") (pintype "passive"))
      (node (ref "C3") (pin "1") (pinfunction "1_1") (pintype "passive"))
      (node (ref "C4") (pin "1") (pinfunction "1_1") (pintype "passive"))
      (node (ref "C5") (pin "2") (pinfunction "2_2") (pintype "passive"))
      (node (ref "C7") (pin "2") (pinfunction "2_2") (pintype "passive"))
      (node (ref "C8") (pin "2") (pinfunction "2_2") (pintype "passive"))
      (node (ref "C9") (pin "2") (pinfunction "2_2") (pintype "passive"))
      (node (ref "D1") (pin "2") (pinfunction "10_2") (pintype "passive"))
      (node (ref "DA1") (pin "2") (pinfunction "NC_2") (pintype "passive"))
      (node (ref "DA1") (pin "3") (pinfunction "NC_3") (pintype "passive"))
      (node (ref "DA1") (pin "6") (pinfunction "GND_6") (pintype "passive"))
      (node (ref "DA1") (pin "9") (pinfunction "GND_9") (pintype "passive"))
      (node (ref "DA2") (pin "2") (pinfunction "GND_2") (pintype "passive"))
      (node (ref "DA3") (pin "2") (pinfunction "GND_2") (pintype "passive"))
      (node (ref "DA4") (pin "2") (pinfunction "GND_2") (pintype "passive"))
      (node (ref "DA5") (pin "2") (pinfunction "GND_2") (pintype "passive"))
      (node (ref "DA6") (pin "2") (pinfunction "GND_2") (pintype "passive"))
      (node (ref "DA7") (pin "2") (pinfunction "GND_2") (pintype "passive"))
      (node (ref "DA8") (pin "2") (pinfunction "-VIN_2") (pintype "passive"))
      (node (ref "DA9") (pin "1") (pinfunction "-VIN_1") (pintype "passive"))
      (node (ref "DD2") (pin "16") (pinfunction "VSS_16") (pintype "passive"))
      (node (ref "DD2") (pin "32") (pinfunction "VSS_32") (pintype "passive"))
      (node (ref "DD5") (pin "3") (pinfunction "-VIN_3") (pintype "passive"))
      (node (ref "DD6") (pin "2") (pinfunction "GND_2") (pintype "power_in"))
      (node (ref "R10") (pin "2") (pinfunction "2_2") (pintype "passive"))
      (node (ref "R11") (pin "2") (pinfunction "2_2") (pintype "passive"))
      (node (ref "R12") (pin "2") (pinfunction "2_2") (pintype "passive"))
      (node (ref "R13") (pin "2") (pinfunction "2_2") (pintype "passive"))
      (node (ref "R15") (pin "1") (pinfunction "1_1") (pintype "passive"))
      (node (ref "R16") (pin "1") (pinfunction "1_1") (pintype "passive"))
      (node (ref "R17") (pin "2") (pinfunction "2_2") (pintype "passive"))
      (node (ref "R18") (pin "1") (pinfunction "1_1") (pintype "passive"))
      (node (ref "R19") (pin "2") (pinfunction "2_2") (pintype "passive"))
      (node (ref "R20") (pin "1") (pinfunction "1_1") (pintype "passive"))
      (node (ref "R21") (pin "2") (pinfunction "2_2") (pintype "passive"))
      (node (ref "R22") (pin "2") (pinfunction "2_2") (pintype "passive"))
      (node (ref "R23") (pin "2") (pinfunction "2_2") (pintype "passive"))
      (node (ref "R24") (pin "2") (pinfunction "2_2") (pintype "passive"))
      (node (ref "R25") (pin "2") (pinfunction "2_2") (pintype "passive"))
      (node (ref "R26") (pin "2") (pinfunction "2_2") (pintype "passive"))
      (node (ref "R27") (pin "2") (pinfunction "2_2") (pintype "passive"))
      (node (ref "R29") (pin "1") (pinfunction "1_1") (pintype "passive"))
      (node (ref "R30") (pin "1") (pinfunction "1_1") (pintype "passive"))
      (node (ref "R6") (pin "1") (pinfunction "1_1") (pintype "passive"))
      (node (ref "R9") (pin "2") (pinfunction "2_2") (pintype "passive"))
      (node (ref "VD2") (pin "2") (pinfunction "A_2") (pintype "passive"))
      (node (ref "VD3") (pin "2") (pinfunction "ANODE_2") (pintype "passive"))
      (node (ref "VD4") (pin "1") (pinfunction "1_1") (pintype "passive"))
      (node (ref "XP12") (pin "1") (pinfunction "1_1") (pintype "passive"))
    )
    (net (code "59") (name "unconnected-(D1-9-Pad1)") (class "Default")
      (node (ref "D1") (pin "1") (pinfunction "9_1") (pintype "passive"))
    )
    (net (code "60") (name "unconnected-(DA8-TRIM-Pad4)") (class "Default")
      (node (ref "DA8") (pin "4") (pinfunction "TRIM_4") (pintype "passive+no_connect"))
    )
    (net (code "61") (name "unconnected-(DA9-NC-Pad5)") (class "Default")
      (node (ref "DA9") (pin "5") (pinfunction "NC_5") (pintype "passive+no_connect"))
    )
    (net (code "62") (name "unconnected-(DA9-NC-Pad8)") (class "Default")
      (node (ref "DA9") (pin "8") (pinfunction "NC_8") (pintype "passive+no_connect"))
    )
    (net (code "63") (name "unconnected-(DD2-PA0-Pad6)") (class "Default")
      (node (ref "DD2") (pin "6") (pinfunction "PA0_6") (pintype "passive"))
    )
    (net (code "64") (name "unconnected-(DD2-PA8-Pad18)") (class "Default")
      (node (ref "DD2") (pin "18") (pinfunction "PA8_18") (pintype "passive"))
    )
    (net (code "65") (name "unconnected-(DD2-PA11-Pad21)") (class "Default")
      (node (ref "DD2") (pin "21") (pinfunction "PA11_21") (pintype "passive"))
    )
    (net (code "66") (name "unconnected-(DD2-PA12-Pad22)") (class "Default")
      (node (ref "DD2") (pin "22") (pinfunction "PA12_22") (pintype "passive"))
    )
    (net (code "67") (name "unconnected-(DD2-PA15-Pad25)") (class "Default")
      (node (ref "DD2") (pin "25") (pinfunction "PA15_25") (pintype "passive"))
    )
    (net (code "68") (name "unconnected-(DD2-PB0-Pad14)") (class "Default")
      (node (ref "DD2") (pin "14") (pinfunction "PB0_14") (pintype "passive"))
    )
    (net (code "69") (name "unconnected-(DD2-PB1-Pad15)") (class "Default")
      (node (ref "DD2") (pin "15") (pinfunction "PB1_15") (pintype "passive"))
    )
  )
)
